# Stepper_Motor_Driver.net
KiCad netlist of a schematic drawn in Altium Designer
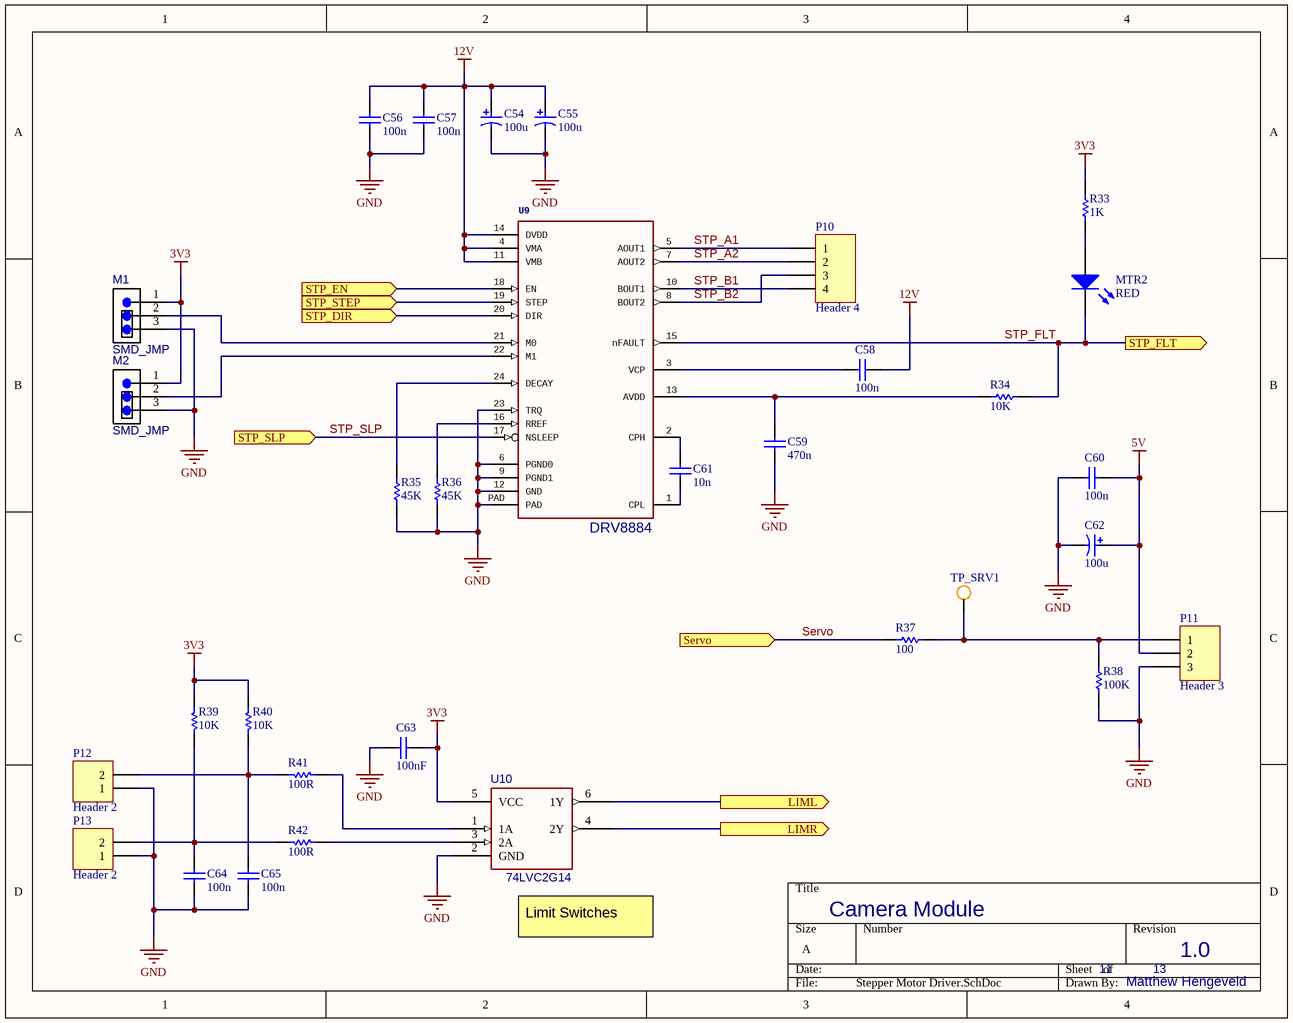
[diagram p0: Stepper Motor Driver.SchDoc]

(export (version "E")
  (design (tool "Eeschema 10.0.6"))
  (components
    (comp (ref "C54")
      (value "100u")
      (footprint "SMD-CAP-0606")
      (fields (field (name "PARTNUMBER") "UUD1V101MNL1GS") (field (name "MANUFACTURER") "Nichicon"))
      (libsource (lib "Hengeveld") (part "CAP-EL-0606-SMD"))
    )
    (comp (ref "C55")
      (value "100u")
      (footprint "SMD-CAP-0606")
      (fields (field (name "PARTNUMBER") "UUD1V101MNL1GS") (field (name "MANUFACTURER") "Nichicon"))
      (libsource (lib "Hengeveld") (part "CAP-EL-0606-SMD"))
    )
    (comp (ref "C56")
      (value "100n")
      (footprint "CAPC1608X87X35LL15T15")
      (fields (field (name "PART NUMBER") "C0603X104K5RACTU") (field (name "MANUFACTURER") "Kemet"))
      (libsource (lib "Altium Content Vault") (part "CAP"))
    )
    (comp (ref "C57")
      (value "100n")
      (footprint "CAPC1608X87X35LL15T15")
      (fields (field (name "PART NUMBER") "C0603X104K5RACTU") (field (name "MANUFACTURER") "Kemet"))
      (libsource (lib "Altium Content Vault") (part "CAP"))
    )
    (comp (ref "C58")
      (value "100n")
      (footprint "CAPC1608X87X35LL15T15")
      (fields (field (name "PART NUMBER") "C0603X104K5RACTU") (field (name "MANUFACTURER") "Kemet"))
      (libsource (lib "Altium Content Vault") (part "CAP"))
    )
    (comp (ref "C59")
      (value "470n")
      (footprint "CAPC1608X90X35LL10T15")
      (fields (field (name "MANUFACTURER") "Murata") (field (name "PART NUMBER") "GRM188R71C474KA88D"))
      (libsource (lib "Altium Content Vault") (part "CAP"))
    )
    (comp (ref "C60")
      (value "100n")
      (footprint "CAPC1608X87X35LL15T15")
      (fields (field (name "PART NUMBER") "C0603X104K5RACTU") (field (name "MANUFACTURER") "Kemet"))
      (libsource (lib "Altium Content Vault") (part "CAP"))
    )
    (comp (ref "C61")
      (value "10n")
      (footprint "CAPC1608X87X35LL15T15")
      (fields (field (name "MANUFACTURER") "Kemet") (field (name "PART NUMBER") "C0603C103K1RACTU"))
      (libsource (lib "Altium Content Vault") (part "CAP"))
    )
    (comp (ref "C62")
      (value "100u")
      (footprint "SMD-CAP-0606")
      (fields (field (name "PARTNUMBER") "UUD1V101MNL1GS") (field (name "MANUFACTURER") "Nichicon"))
      (libsource (lib "Hengeveld") (part "CAP-EL-0606-SMD"))
    )
    (comp (ref "C63")
      (value "100nF")
      (footprint "CAPC1608X92X38LL15T08")
      (fields (field (name "PART NUMBER") "VJ0603Y104KNXAO") (field (name "MANUFACTURER") "Vitramon"))
      (libsource (lib "Altium Content Vault") (part "CAP"))
    )
    (comp (ref "C64")
      (value "100n")
      (footprint "CAPC1608X87X35LL15T15")
      (fields (field (name "PART NUMBER") "C0603X104K5RACTU") (field (name "MANUFACTURER") "Kemet"))
      (libsource (lib "Altium Content Vault") (part "CAP"))
    )
    (comp (ref "C65")
      (value "100n")
      (footprint "CAPC1608X87X35LL15T15")
      (fields (field (name "PART NUMBER") "C0603X104K5RACTU") (field (name "MANUFACTURER") "Kemet"))
      (libsource (lib "Altium Content Vault") (part "CAP"))
    )
    (comp (ref "M1")
      (value "SMD_JMP")
      (footprint "0603_JUMPER")
      (libsource (lib "Hengeveld") (part "SMD_JMP"))
    )
    (comp (ref "M2")
      (value "SMD_JMP")
      (footprint "0603_JUMPER")
      (libsource (lib "Hengeveld") (part "SMD_JMP"))
    )
    (comp (ref "MTR2")
      (value "RED")
      (footprint "0805_A")
      (description "SMD mono-color Chip LED, WL-SMCW, Red")
      (fields (field (name "PARTNUMBER") "150080RS75000") (field (name "MANUFACTURER") "Wuerth Elektronik"))
      (libsource (lib "Altium Content Vault") (part "WE-LED_K1A2-2"))
    )
    (comp (ref "P10")
      (value "Header 4")
      (footprint "HDR1X4")
      (description "Header, 4-Pin")
      (fields (field (name "PUBLISHER") "Altium Limited"))
      (libsource (lib "Hengeveld") (part "Header 4"))
    )
    (comp (ref "P11")
      (value "Header 3")
      (footprint "HDR1X3")
      (description "Header, 3-Pin")
      (fields (field (name "PUBLISHER") "Altium Limited"))
      (libsource (lib "Hengeveld") (part "Header 3"))
    )
    (comp (ref "P12")
      (value "Header 2")
      (footprint "HDR1X2")
      (description "Header, 2-Pin")
      (fields (field (name "PUBLISHER") "Altium Limited"))
      (libsource (lib "Hengeveld") (part "Header 2"))
    )
    (comp (ref "P13")
      (value "Header 2")
      (footprint "HDR1X2")
      (description "Header, 2-Pin")
      (fields (field (name "PUBLISHER") "Altium Limited"))
      (libsource (lib "Hengeveld") (part "Header 2"))
    )
    (comp (ref "R33")
      (value "1K")
      (footprint "RESC1608X55X30LL15T15")
      (fields (field (name "MANUFACTURER") "Panasonic") (field (name "PART NUMBER") "ERJ-3GEYJ103V"))
      (libsource (lib "Altium Content Vault") (part "RES"))
    )
    (comp (ref "R34")
      (value "10K")
      (footprint "RESC1608X55X30LL15T15")
      (fields (field (name "MANUFACTURER") "Panasonic") (field (name "PART NUMBER") "ERJ-3GEYJ103V"))
      (libsource (lib "Altium Content Vault") (part "RES"))
    )
    (comp (ref "R35")
      (value "45K")
      (footprint "RESC1608X55X30LL15T15")
      (fields (field (name "MANUFACTURER") "Panasonic") (field (name "PART NUMBER") "ERJ-3GEYJ103V"))
      (libsource (lib "Altium Content Vault") (part "RES"))
    )
    (comp (ref "R36")
      (value "45K")
      (footprint "RESC1608X55X30LL15T15")
      (fields (field (name "MANUFACTURER") "Panasonic") (field (name "PART NUMBER") "ERJ-3GEYJ103V"))
      (libsource (lib "Altium Content Vault") (part "RES"))
    )
    (comp (ref "R37")
      (value "100")
      (footprint "RESC1608X55X30LL15T15")
      (fields (field (name "MANUFACTURER") "Panasonic") (field (name "PART NUMBER") "ERJ-3GEYJ103V"))
      (libsource (lib "Altium Content Vault") (part "RES"))
    )
    (comp (ref "R38")
      (value "100K")
      (footprint "RESC1608X55X30LL15T15")
      (fields (field (name "MANUFACTURER") "Panasonic") (field (name "PART NUMBER") "ERJ-3GEYJ103V"))
      (libsource (lib "Altium Content Vault") (part "RES"))
    )
    (comp (ref "R39")
      (value "10K")
      (footprint "RESC1608X55X30LL15T15")
      (fields (field (name "MANUFACTURER") "Panasonic") (field (name "PART NUMBER") "ERJ-3GEYJ103V"))
      (libsource (lib "Altium Content Vault") (part "RES"))
    )
    (comp (ref "R40")
      (value "10K")
      (footprint "RESC1608X55X30LL15T15")
      (fields (field (name "MANUFACTURER") "Panasonic") (field (name "PART NUMBER") "ERJ-3GEYJ103V"))
      (libsource (lib "Altium Content Vault") (part "RES"))
    )
    (comp (ref "R41")
      (value "100R")
      (footprint "RESC1608X55X30LL15T15")
      (fields (field (name "MANUFACTURER") "Panasonic") (field (name "PART NUMBER") "ERJ-3GEYJ103V"))
      (libsource (lib "Altium Content Vault") (part "RES"))
    )
    (comp (ref "R42")
      (value "100R")
      (footprint "RESC1608X55X30LL15T15")
      (fields (field (name "MANUFACTURER") "Panasonic") (field (name "PART NUMBER") "ERJ-3GEYJ103V"))
      (libsource (lib "Altium Content Vault") (part "RES"))
    )
    (comp (ref "TP_SRV1")
      (value "Test point")
      (footprint "SMD Test Hook")
      (libsource (lib "Hengeveld") (part "Test Point"))
    )
    (comp (ref "U9") (value "DRV8884") (footprint "TI-PWP24") (libsource (lib "Hengeveld") (part "DRV8884")))
    (comp (ref "U10")
      (value "74LVC2G14")
      (footprint "ONSC-SOT-363-6-419B-02_V")
      (libsource (lib "Hengeveld") (part "74LVC2G14"))
    )
  )
  (nets
    (net (code "1") (name "/LIML") (class "Default")
      (node (ref "U10") (pin "6") (pinfunction "1Y_6") (pintype "output"))
    )
    (net (code "2") (name "/LIMR") (class "Default")
      (node (ref "U10") (pin "4") (pinfunction "2Y_4") (pintype "output"))
    )
    (net (code "3") (name "/STP_A1") (class "Default")
      (node (ref "P10") (pin "1") (pinfunction "1_1") (pintype "passive"))
      (node (ref "U9") (pin "5") (pinfunction "AOUT1_5") (pintype "output"))
    )
    (net (code "4") (name "/STP_A2") (class "Default")
      (node (ref "P10") (pin "2") (pinfunction "2_2") (pintype "passive"))
      (node (ref "U9") (pin "7") (pinfunction "AOUT2_7") (pintype "output"))
    )
    (net (code "5") (name "/STP_B1") (class "Default")
      (node (ref "P10") (pin "4") (pinfunction "4_4") (pintype "passive"))
      (node (ref "U9") (pin "10") (pinfunction "BOUT1_10") (pintype "output"))
    )
    (net (code "6") (name "/STP_B2") (class "Default")
      (node (ref "P10") (pin "3") (pinfunction "3_3") (pintype "passive"))
      (node (ref "U9") (pin "8") (pinfunction "BOUT2_8") (pintype "output"))
    )
    (net (code "7") (name "/STP_DIR") (class "Default")
      (node (ref "U9") (pin "20") (pinfunction "DIR_20") (pintype "input"))
    )
    (net (code "8") (name "/STP_EN") (class "Default")
      (node (ref "U9") (pin "18") (pinfunction "EN_18") (pintype "input"))
    )
    (net (code "9") (name "/STP_FLT") (class "Default")
      (node (ref "MTR2") (pin "1") (pinfunction "K_1") (pintype "passive"))
      (node (ref "R34") (pin "2") (pinfunction "2_2") (pintype "passive"))
      (node (ref "U9") (pin "15") (pinfunction "nFAULT_15") (pintype "output"))
    )
    (net (code "10") (name "/STP_SLP") (class "Default")
      (node (ref "U9") (pin "17") (pinfunction "NSLEEP_17") (pintype "input"))
    )
    (net (code "11") (name "/STP_STEP") (class "Default")
      (node (ref "U9") (pin "19") (pinfunction "STEP_19") (pintype "input"))
    )
    (net (code "12") (name "/Servo") (class "Default")
      (node (ref "R37") (pin "2") (pinfunction "2_2") (pintype "passive"))
    )
    (net (code "13") (name "3V3") (class "Default")
      (node (ref "C63") (pin "2") (pinfunction "2_2") (pintype "passive"))
      (node (ref "M1") (pin "1") (pinfunction "1_1") (pintype "passive"))
      (node (ref "M2") (pin "1") (pinfunction "1_1") (pintype "passive"))
      (node (ref "R33") (pin "1") (pinfunction "1_1") (pintype "passive"))
      (node (ref "R39") (pin "1") (pinfunction "1_1") (pintype "passive"))
      (node (ref "R40") (pin "1") (pinfunction "1_1") (pintype "passive"))
      (node (ref "U10") (pin "5") (pinfunction "VCC_5") (pintype "power_in"))
    )
    (net (code "14") (name "5V") (class "Default")
      (node (ref "C60") (pin "1") (pinfunction "1_1") (pintype "passive"))
      (node (ref "C62") (pin "1") (pinfunction "1_1") (pintype "passive"))
      (node (ref "P11") (pin "2") (pinfunction "2_2") (pintype "passive"))
    )
    (net (code "15") (name "12V") (class "Default")
      (node (ref "C54") (pin "1") (pinfunction "1_1") (pintype "passive"))
      (node (ref "C55") (pin "1") (pinfunction "1_1") (pintype "passive"))
      (node (ref "C56") (pin "2") (pinfunction "2_2") (pintype "passive"))
      (node (ref "C57") (pin "2") (pinfunction "2_2") (pintype "passive"))
      (node (ref "C58") (pin "1") (pinfunction "1_1") (pintype "passive"))
      (node (ref "U9") (pin "11") (pinfunction "VMB_11") (pintype "power_in"))
      (node (ref "U9") (pin "14") (pinfunction "DVDD_14") (pintype "power_in"))
      (node (ref "U9") (pin "4") (pinfunction "VMA_4") (pintype "power_in"))
    )
    (net (code "16") (name "GND") (class "Default")
      (node (ref "C54") (pin "2") (pinfunction "2_2") (pintype "passive"))
      (node (ref "C55") (pin "2") (pinfunction "2_2") (pintype "passive"))
      (node (ref "C56") (pin "1") (pinfunction "1_1") (pintype "passive"))
      (node (ref "C57") (pin "1") (pinfunction "1_1") (pintype "passive"))
      (node (ref "C59") (pin "1") (pinfunction "1_1") (pintype "passive"))
      (node (ref "C60") (pin "2") (pinfunction "2_2") (pintype "passive"))
      (node (ref "C62") (pin "2") (pinfunction "2_2") (pintype "passive"))
      (node (ref "C63") (pin "1") (pinfunction "1_1") (pintype "passive"))
      (node (ref "C64") (pin "2") (pinfunction "2_2") (pintype "passive"))
      (node (ref "C65") (pin "2") (pinfunction "2_2") (pintype "passive"))
      (node (ref "M1") (pin "3") (pinfunction "3_3") (pintype "passive"))
      (node (ref "M2") (pin "3") (pinfunction "3_3") (pintype "passive"))
      (node (ref "P11") (pin "3") (pinfunction "3_3") (pintype "passive"))
      (node (ref "P12") (pin "1") (pinfunction "1_1") (pintype "passive"))
      (node (ref "P13") (pin "1") (pinfunction "1_1") (pintype "passive"))
      (node (ref "R35") (pin "2") (pinfunction "2_2") (pintype "passive"))
      (node (ref "R36") (pin "2") (pinfunction "2_2") (pintype "passive"))
      (node (ref "R38") (pin "2") (pinfunction "2_2") (pintype "passive"))
      (node (ref "U10") (pin "2") (pinfunction "GND_2") (pintype "power_in"))
      (node (ref "U9") (pin "12") (pinfunction "GND_12") (pintype "power_in"))
      (node (ref "U9") (pin "23") (pinfunction "TRQ_23") (pintype "input"))
      (node (ref "U9") (pin "6") (pinfunction "PGND0_6") (pintype "power_in"))
      (node (ref "U9") (pin "9") (pinfunction "PGND1_9") (pintype "power_in"))
      (node (ref "U9") (pin "PAD") (pinfunction "PAD_PAD") (pintype "power_in"))
    )
    (net (code "17") (name "Net-(C64-Pad1)") (class "Default")
      (node (ref "C64") (pin "1") (pinfunction "1_1") (pintype "passive"))
      (node (ref "P13") (pin "2") (pinfunction "2_2") (pintype "passive"))
      (node (ref "R39") (pin "2") (pinfunction "2_2") (pintype "passive"))
      (node (ref "R42") (pin "1") (pinfunction "1_1") (pintype "passive"))
    )
    (net (code "18") (name "Net-(C65-Pad1)") (class "Default")
      (node (ref "C65") (pin "1") (pinfunction "1_1") (pintype "passive"))
      (node (ref "P12") (pin "2") (pinfunction "2_2") (pintype "passive"))
      (node (ref "R40") (pin "2") (pinfunction "2_2") (pintype "passive"))
      (node (ref "R41") (pin "1") (pinfunction "1_1") (pintype "passive"))
    )
    (net (code "19") (name "Net-(MTR2-A)") (class "Default")
      (node (ref "MTR2") (pin "2") (pinfunction "A_2") (pintype "passive"))
      (node (ref "R33") (pin "2") (pinfunction "2_2") (pintype "passive"))
    )
    (net (code "20") (name "Net-(TP_SRV1-point)") (class "Default")
      (node (ref "P11") (pin "1") (pinfunction "1_1") (pintype "passive"))
      (node (ref "R37") (pin "1") (pinfunction "1_1") (pintype "passive"))
      (node (ref "R38") (pin "1") (pinfunction "1_1") (pintype "passive"))
      (node (ref "TP_SRV1") (pin "1") (pinfunction "point_1") (pintype "passive"))
    )
    (net (code "21") (name "Net-(U9-AVDD)") (class "Default")
      (node (ref "C59") (pin "2") (pinfunction "2_2") (pintype "passive"))
      (node (ref "R34") (pin "1") (pinfunction "1_1") (pintype "passive"))
      (node (ref "U9") (pin "13") (pinfunction "AVDD_13") (pintype "power_in"))
    )
    (net (code "22") (name "Net-(U9-CPH)") (class "Default")
      (node (ref "C61") (pin "2") (pinfunction "2_2") (pintype "passive"))
      (node (ref "U9") (pin "2") (pinfunction "CPH_2") (pintype "power_in"))
    )
    (net (code "23") (name "Net-(U9-CPL)") (class "Default")
      (node (ref "C61") (pin "1") (pinfunction "1_1") (pintype "passive"))
      (node (ref "U9") (pin "1") (pinfunction "CPL_1") (pintype "power_in"))
    )
    (net (code "24") (name "Net-(U9-DECAY)") (class "Default")
      (node (ref "R35") (pin "1") (pinfunction "1_1") (pintype "passive"))
      (node (ref "U9") (pin "24") (pinfunction "DECAY_24") (pintype "input"))
    )
    (net (code "25") (name "Net-(U9-M0)") (class "Default")
      (node (ref "M1") (pin "2") (pinfunction "2_2") (pintype "passive"))
      (node (ref "U9") (pin "21") (pinfunction "M0_21") (pintype "input"))
    )
    (net (code "26") (name "Net-(U9-M1)") (class "Default")
      (node (ref "M2") (pin "2") (pinfunction "2_2") (pintype "passive"))
      (node (ref "U9") (pin "22") (pinfunction "M1_22") (pintype "input"))
    )
    (net (code "27") (name "Net-(U9-RREF)") (class "Default")
      (node (ref "R36") (pin "1") (pinfunction "1_1") (pintype "passive"))
      (node (ref "U9") (pin "16") (pinfunction "RREF_16") (pintype "input"))
    )
    (net (code "28") (name "Net-(U9-VCP)") (class "Default")
      (node (ref "C58") (pin "2") (pinfunction "2_2") (pintype "passive"))
      (node (ref "U9") (pin "3") (pinfunction "VCP_3") (pintype "power_in"))
    )
    (net (code "29") (name "Net-(U10-1A)") (class "Default")
      (node (ref "R41") (pin "2") (pinfunction "2_2") (pintype "passive"))
      (node (ref "U10") (pin "1") (pinfunction "1A_1") (pintype "input"))
    )
    (net (code "30") (name "Net-(U10-2A)") (class "Default")
      (node (ref "R42") (pin "2") (pinfunction "2_2") (pintype "passive"))
      (node (ref "U10") (pin "3") (pinfunction "2A_3") (pintype "input"))
    )
  )
)
